# Experiment4.net
KiCad netlist of a schematic drawn in EAGLE
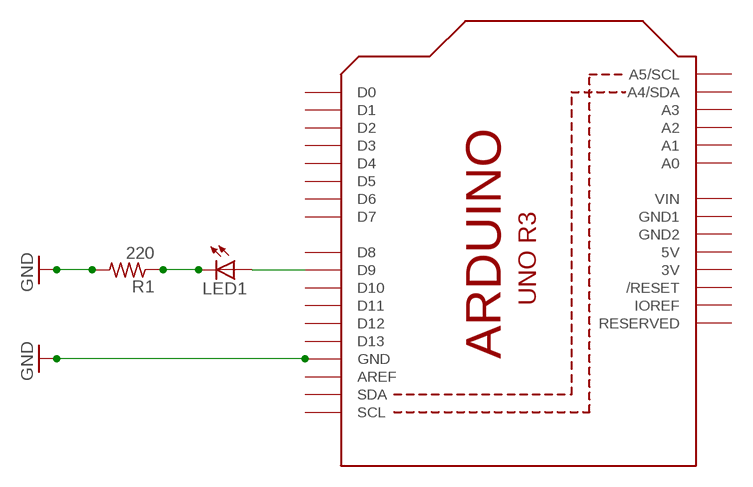
[diagram p0: schematic, sheet 1]

(export (version "E")
  (design (tool "Eeschema 10.0.6"))
  (components
    (comp (ref "LED1")
      (value "LED5MM")
      (footprint "eagle-import:LED5MM")
      (libsource (lib "eagle-import") (part "LED5MM"))
    )
    (comp (ref "R1")
      (value "220")
      (footprint "eagle-import:0204_5")
      (libsource (lib "eagle-import") (part "R-US_0204/5"))
    )
    (comp (ref "U1")
      (value "ARDUINOR3-DIMENSION")
      (footprint "eagle-import:ARDUINOR3")
      (libsource (lib "eagle-import") (part "ARDUINOR3-DIMENSION"))
    )
  )
  (nets
    (net (code "1") (name "/3V") (class "Default")
      (node (ref "U1") (pin "3V") (pinfunction "3V_3V") (pintype "power_in"))
    )
    (net (code "2") (name "/5V") (class "Default")
      (node (ref "U1") (pin "5V") (pinfunction "5V_5V") (pintype "power_in"))
    )
    (net (code "3") (name "/GND1") (class "Default")
      (node (ref "U1") (pin "GND1") (pinfunction "GND1_GND1") (pintype "power_in"))
    )
    (net (code "4") (name "/GND2") (class "Default")
      (node (ref "U1") (pin "GND2") (pinfunction "GND2_GND2") (pintype "power_in"))
    )
    (net (code "5") (name "/VIN") (class "Default")
      (node (ref "U1") (pin "VIN") (pinfunction "VIN_VIN") (pintype "power_in"))
    )
    (net (code "6") (name "GND") (class "Default")
      (node (ref "R1") (pin "2") (pinfunction "2_2") (pintype "passive"))
      (node (ref "U1") (pin "GND") (pinfunction "GND_GND") (pintype "power_in"))
    )
    (net (code "7") (name "Net-(LED1-C)") (class "Default")
      (node (ref "LED1") (pin "K") (pinfunction "C_K") (pintype "passive"))
      (node (ref "R1") (pin "1") (pinfunction "1_1") (pintype "passive"))
    )
    (net (code "8") (name "Net-(LED1-PadA)") (class "Default")
      (node (ref "LED1") (pin "A") (pinfunction "A_A") (pintype "passive"))
      (node (ref "U1") (pin "D9") (pinfunction "D9_D9") (pintype "bidirectional"))
    )
    (net (code "9") (name "unconnected-(U1-A4{slash}SDA-PadA4)") (class "Default")
      (node (ref "U1") (pin "A4") (pinfunction "A4/SDA_A4") (pintype "bidirectional"))
    )
    (net (code "10") (name "unconnected-(U1-A5{slash}SCL-PadA5)") (class "Default")
      (node (ref "U1") (pin "A5") (pinfunction "A5/SCL_A5") (pintype "bidirectional"))
    )
    (net (code "11") (name "unconnected-(U1-PadA0)") (class "Default")
      (node (ref "U1") (pin "A0") (pinfunction "A0_A0") (pintype "bidirectional"))
    )
    (net (code "12") (name "unconnected-(U1-PadA1)") (class "Default")
      (node (ref "U1") (pin "A1") (pinfunction "A1_A1") (pintype "bidirectional"))
    )
    (net (code "13") (name "unconnected-(U1-PadA2)") (class "Default")
      (node (ref "U1") (pin "A2") (pinfunction "A2_A2") (pintype "bidirectional"))
    )
    (net (code "14") (name "unconnected-(U1-PadA3)") (class "Default")
      (node (ref "U1") (pin "A3") (pinfunction "A3_A3") (pintype "bidirectional"))
    )
    (net (code "15") (name "unconnected-(U1-PadAREF)") (class "Default")
      (node (ref "U1") (pin "AREF") (pinfunction "AREF_AREF") (pintype "bidirectional"))
    )
    (net (code "16") (name "unconnected-(U1-PadD0)") (class "Default")
      (node (ref "U1") (pin "D0") (pinfunction "D0_D0") (pintype "bidirectional"))
    )
    (net (code "17") (name "unconnected-(U1-PadD1)") (class "Default")
      (node (ref "U1") (pin "D1") (pinfunction "D1_D1") (pintype "bidirectional"))
    )
    (net (code "18") (name "unconnected-(U1-PadD2)") (class "Default")
      (node (ref "U1") (pin "D2") (pinfunction "D2_D2") (pintype "bidirectional"))
    )
    (net (code "19") (name "unconnected-(U1-PadD3)") (class "Default")
      (node (ref "U1") (pin "D3") (pinfunction "D3_D3") (pintype "bidirectional"))
    )
    (net (code "20") (name "unconnected-(U1-PadD4)") (class "Default")
      (node (ref "U1") (pin "D4") (pinfunction "D4_D4") (pintype "bidirectional"))
    )
    (net (code "21") (name "unconnected-(U1-PadD5)") (class "Default")
      (node (ref "U1") (pin "D5") (pinfunction "D5_D5") (pintype "bidirectional"))
    )
    (net (code "22") (name "unconnected-(U1-PadD6)") (class "Default")
      (node (ref "U1") (pin "D6") (pinfunction "D6_D6") (pintype "bidirectional"))
    )
    (net (code "23") (name "unconnected-(U1-PadD7)") (class "Default")
      (node (ref "U1") (pin "D7") (pinfunction "D7_D7") (pintype "bidirectional"))
    )
    (net (code "24") (name "unconnected-(U1-PadD8)") (class "Default")
      (node (ref "U1") (pin "D8") (pinfunction "D8_D8") (pintype "bidirectional"))
    )
    (net (code "25") (name "unconnected-(U1-PadD10)") (class "Default")
      (node (ref "U1") (pin "D10") (pinfunction "D10_D10") (pintype "bidirectional"))
    )
    (net (code "26") (name "unconnected-(U1-PadD11)") (class "Default")
      (node (ref "U1") (pin "D11") (pinfunction "D11_D11") (pintype "bidirectional"))
    )
    (net (code "27") (name "unconnected-(U1-PadD12)") (class "Default")
      (node (ref "U1") (pin "D12") (pinfunction "D12_D12") (pintype "bidirectional"))
    )
    (net (code "28") (name "unconnected-(U1-PadD13)") (class "Default")
      (node (ref "U1") (pin "D13") (pinfunction "D13_D13") (pintype "bidirectional"))
    )
    (net (code "29") (name "unconnected-(U1-PadIOREF)") (class "Default")
      (node (ref "U1") (pin "IOREF") (pinfunction "IOREF_IOREF") (pintype "output"))
    )
    (net (code "30") (name "unconnected-(U1-PadRESERVED)") (class "Default")
      (node (ref "U1") (pin "RESERVED") (pinfunction "RESERVED_RESERVED") (pintype "no_connect"))
    )
    (net (code "31") (name "unconnected-(U1-PadSCL)") (class "Default")
      (node (ref "U1") (pin "SCL") (pinfunction "SCL_SCL") (pintype "bidirectional"))
    )
    (net (code "32") (name "unconnected-(U1-PadSDA)") (class "Default")
      (node (ref "U1") (pin "SDA") (pinfunction "SDA_SDA") (pintype "bidirectional"))
    )
    (net (code "33") (name "unconnected-(U1-{slash}RESET-PadRESET)") (class "Default")
      (node (ref "U1") (pin "RESET") (pinfunction "/RESET_RESET") (pintype "bidirectional"))
    )
  )
)
